# ftdi_ok.net
KiCad netlist of a schematic drawn in Altium Designer
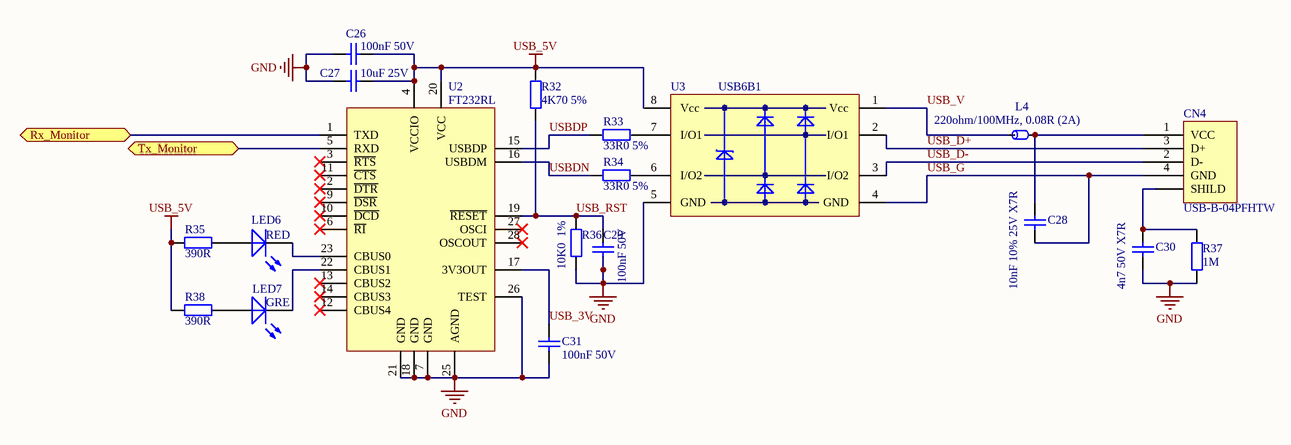
[diagram p0: ftdi_ok.SchDoc]

(export (version "E")
  (design (tool "Eeschema 10.0.6"))
  (components
    (comp (ref "C26")
      (value "100nF 50V")
      (footprint "0805_C")
      (description "SMD kondenzátorok")
      (libsource (lib "MERES") (part "Capacitor_SMD"))
    )
    (comp (ref "C27")
      (value "10uF 25V")
      (footprint "1206_C")
      (description "SMD kondenzátorok")
      (libsource (lib "MERES") (part "Capacitor_SMD"))
    )
    (comp (ref "C28")
      (value "10nF 10% 25V X7R")
      (footprint "1210_C")
      (description "SMD kondenzátorok")
      (libsource (lib "MERES") (part "Capacitor_SMD"))
    )
    (comp (ref "C29")
      (value "100nF 50V")
      (footprint "0805_C")
      (description "SMD kondenzátorok")
      (libsource (lib "MERES") (part "Capacitor_SMD"))
    )
    (comp (ref "C30")
      (value "4n7 50V X7R")
      (footprint "0805_C")
      (description "SMD kondenzátorok")
      (libsource (lib "MERES") (part "Capacitor_SMD"))
    )
    (comp (ref "C31")
      (value "100nF 50V")
      (footprint "0805_C")
      (description "SMD kondenzátorok")
      (libsource (lib "MERES") (part "Capacitor_SMD"))
    )
    (comp (ref "CN4") (value "USB-B-04PFHTW") (footprint "USB-B") (libsource (lib "MERES") (part "USB-B")))
    (comp (ref "L4")
      (value "220ohm/100MHz, 0.08R (2A)")
      (footprint "0805_R")
      (description "SMD Ferrit Bead 220ohm/100MHz")
      (libsource (lib "MERES") (part "Ferrit Bead"))
    )
    (comp (ref "LED6")
      (value "RED")
      (footprint "FP_LED_TH_RED")
      (description "LED")
      (libsource (lib "hallglib") (part "LED"))
    )
    (comp (ref "LED7")
      (value "GRE")
      (footprint "FP_LED_TH_GREEN")
      (description "LED")
      (libsource (lib "hallglib") (part "LED"))
    )
    (comp (ref "R32") (value "4K70 5%") (footprint "AXIAL-0.3") (libsource (lib "") (part "Resistor_2")))
    (comp (ref "R33")
      (value "33R0 5%")
      (footprint "AXIAL-0.3")
      (libsource (lib "hallglib") (part "Resistor"))
    )
    (comp (ref "R34")
      (value "33R0 5%")
      (footprint "AXIAL-0.3")
      (libsource (lib "hallglib") (part "Resistor"))
    )
    (comp (ref "R35") (value "390R") (footprint "AXIAL-0.3") (libsource (lib "") (part "Resistor_1")))
    (comp (ref "R36") (value "10K0  1%") (footprint "AXIAL-0.3") (libsource (lib "") (part "Resistor_2")))
    (comp (ref "R37") (value "1M") (footprint "0805_R") (libsource (lib "") (part "Resistor_3")))
    (comp (ref "R38") (value "390R") (footprint "AXIAL-0.3") (libsource (lib "") (part "Resistor_1")))
    (comp (ref "U2")
      (value "FT232RL")
      (footprint "SSOP-28")
      (description "USB - UART IC")
      (libsource (lib "MERES") (part "FT232RL"))
    )
    (comp (ref "U3") (value "USB6B1") (footprint "SO-8") (libsource (lib "MERES") (part "USB6B1")))
  )
  (nets
    (net (code "1") (name "/Rx_Monitor") (class "Default")
      (node (ref "U2") (pin "1") (pinfunction "TXD_1") (pintype "passive"))
    )
    (net (code "2") (name "/Tx_Monitor") (class "Default")
      (node (ref "U2") (pin "5") (pinfunction "RXD_5") (pintype "passive"))
    )
    (net (code "3") (name "/USBDN") (class "Default")
      (node (ref "R34") (pin "2") (pinfunction "2_2") (pintype "passive"))
      (node (ref "U2") (pin "16") (pinfunction "USBDM_16") (pintype "passive"))
    )
    (net (code "4") (name "/USBDP") (class "Default")
      (node (ref "R33") (pin "2") (pinfunction "2_2") (pintype "passive"))
      (node (ref "U2") (pin "15") (pinfunction "USBDP_15") (pintype "passive"))
    )
    (net (code "5") (name "/USB_3V") (class "Default")
      (node (ref "C31") (pin "1") (pinfunction "1_1") (pintype "passive"))
      (node (ref "U2") (pin "17") (pinfunction "3V3OUT_17") (pintype "passive"))
    )
    (net (code "6") (name "/USB_D+") (class "Default")
      (node (ref "CN4") (pin "3") (pinfunction "D+_3") (pintype "passive"))
      (node (ref "U3") (pin "2") (pinfunction "I/O1_2") (pintype "passive"))
    )
    (net (code "7") (name "/USB_D-") (class "Default")
      (node (ref "CN4") (pin "2") (pinfunction "D-_2") (pintype "passive"))
      (node (ref "U3") (pin "3") (pinfunction "I/O2_3") (pintype "passive"))
    )
    (net (code "8") (name "/USB_G") (class "Default")
      (node (ref "C28") (pin "2") (pinfunction "2_2") (pintype "passive"))
      (node (ref "CN4") (pin "4") (pinfunction "GND_4") (pintype "passive"))
      (node (ref "U3") (pin "4") (pinfunction "GND_4") (pintype "passive"))
    )
    (net (code "9") (name "/USB_RST") (class "Default")
      (node (ref "C29") (pin "1") (pinfunction "1_1") (pintype "passive"))
      (node (ref "R32") (pin "1") (pinfunction "1_1") (pintype "passive"))
      (node (ref "R36") (pin "2") (pinfunction "2_2") (pintype "passive"))
      (node (ref "U2") (pin "19") (pinfunction "~{RESET}_19") (pintype "passive"))
    )
    (net (code "10") (name "/USB_V") (class "Default")
      (node (ref "L4") (pin "2") (pinfunction "2_2") (pintype "passive"))
      (node (ref "U3") (pin "1") (pinfunction "Vcc_1") (pintype "passive"))
    )
    (net (code "11") (name "GND") (class "Default")
      (node (ref "C26") (pin "2") (pinfunction "2_2") (pintype "passive"))
      (node (ref "C27") (pin "2") (pinfunction "2_2") (pintype "passive"))
      (node (ref "C29") (pin "2") (pinfunction "2_2") (pintype "passive"))
      (node (ref "C30") (pin "2") (pinfunction "2_2") (pintype "passive"))
      (node (ref "C31") (pin "2") (pinfunction "2_2") (pintype "passive"))
      (node (ref "R36") (pin "1") (pinfunction "1_1") (pintype "passive"))
      (node (ref "R37") (pin "2") (pinfunction "2_2") (pintype "passive"))
      (node (ref "U2") (pin "18") (pinfunction "GND_18") (pintype "passive"))
      (node (ref "U2") (pin "21") (pinfunction "GND_21") (pintype "passive"))
      (node (ref "U2") (pin "25") (pinfunction "AGND_25") (pintype "passive"))
      (node (ref "U2") (pin "26") (pinfunction "TEST_26") (pintype "passive"))
      (node (ref "U2") (pin "7") (pinfunction "GND_7") (pintype "passive"))
      (node (ref "U3") (pin "5") (pinfunction "GND_5") (pintype "passive"))
    )
    (net (code "12") (name "Net-(CN4-SHILD)") (class "Default")
      (node (ref "C30") (pin "1") (pinfunction "1_1") (pintype "passive"))
      (node (ref "CN4") (pin "0") (pinfunction "SHILD_0") (pintype "passive"))
      (node (ref "R37") (pin "1") (pinfunction "1_1") (pintype "passive"))
    )
    (net (code "13") (name "Net-(CN4-VCC)") (class "Default")
      (node (ref "C28") (pin "1") (pinfunction "1_1") (pintype "passive"))
      (node (ref "CN4") (pin "1") (pinfunction "VCC_1") (pintype "passive"))
      (node (ref "L4") (pin "1") (pinfunction "1_1") (pintype "passive"))
    )
    (net (code "14") (name "Net-(LED6-A)") (class "Default")
      (node (ref "LED6") (pin "1") (pinfunction "A_1") (pintype "passive"))
      (node (ref "R35") (pin "2") (pinfunction "2_2") (pintype "passive"))
    )
    (net (code "15") (name "Net-(LED6-K)") (class "Default")
      (node (ref "LED6") (pin "2") (pinfunction "K_2") (pintype "passive"))
      (node (ref "U2") (pin "23") (pinfunction "CBUS0_23") (pintype "passive"))
    )
    (net (code "16") (name "Net-(LED7-A)") (class "Default")
      (node (ref "LED7") (pin "1") (pinfunction "A_1") (pintype "passive"))
      (node (ref "R38") (pin "2") (pinfunction "2_2") (pintype "passive"))
    )
    (net (code "17") (name "Net-(LED7-K)") (class "Default")
      (node (ref "LED7") (pin "2") (pinfunction "K_2") (pintype "passive"))
      (node (ref "U2") (pin "22") (pinfunction "CBUS1_22") (pintype "passive"))
    )
    (net (code "18") (name "Net-(R33-Pad1)") (class "Default")
      (node (ref "R33") (pin "1") (pinfunction "1_1") (pintype "passive"))
      (node (ref "U3") (pin "7") (pinfunction "I/O1_7") (pintype "passive"))
    )
    (net (code "19") (name "Net-(R34-Pad1)") (class "Default")
      (node (ref "R34") (pin "1") (pinfunction "1_1") (pintype "passive"))
      (node (ref "U3") (pin "6") (pinfunction "I/O2_6") (pintype "passive"))
    )
    (net (code "20") (name "USB_5V") (class "Default")
      (node (ref "C26") (pin "1") (pinfunction "1_1") (pintype "passive"))
      (node (ref "C27") (pin "1") (pinfunction "1_1") (pintype "passive"))
      (node (ref "R32") (pin "2") (pinfunction "2_2") (pintype "passive"))
      (node (ref "R35") (pin "1") (pinfunction "1_1") (pintype "passive"))
      (node (ref "R38") (pin "1") (pinfunction "1_1") (pintype "passive"))
      (node (ref "U2") (pin "20") (pinfunction "VCC_20") (pintype "passive"))
      (node (ref "U2") (pin "4") (pinfunction "VCCIO_4") (pintype "passive"))
      (node (ref "U3") (pin "8") (pinfunction "Vcc_8") (pintype "passive"))
    )
    (net (code "21") (name "unconnected-(U2-CBUS2-Pad13)") (class "Default")
      (node (ref "U2") (pin "13") (pinfunction "CBUS2_13") (pintype "passive+no_connect"))
    )
    (net (code "22") (name "unconnected-(U2-CBUS3-Pad14)") (class "Default")
      (node (ref "U2") (pin "14") (pinfunction "CBUS3_14") (pintype "passive+no_connect"))
    )
    (net (code "23") (name "unconnected-(U2-CBUS4-Pad12)") (class "Default")
      (node (ref "U2") (pin "12") (pinfunction "CBUS4_12") (pintype "passive+no_connect"))
    )
    (net (code "24") (name "unconnected-(U2-OSCI-Pad27)") (class "Default")
      (node (ref "U2") (pin "27") (pinfunction "OSCI_27") (pintype "passive+no_connect"))
    )
    (net (code "25") (name "unconnected-(U2-OSCOUT-Pad28)") (class "Default")
      (node (ref "U2") (pin "28") (pinfunction "OSCOUT_28") (pintype "passive+no_connect"))
    )
    (net (code "26") (name "unconnected-(U2-~{CTS}-Pad11)") (class "Default")
      (node (ref "U2") (pin "11") (pinfunction "~{CTS}_11") (pintype "passive+no_connect"))
    )
    (net (code "27") (name "unconnected-(U2-~{DCD}-Pad10)") (class "Default")
      (node (ref "U2") (pin "10") (pinfunction "~{DCD}_10") (pintype "passive+no_connect"))
    )
    (net (code "28") (name "unconnected-(U2-~{DSR}-Pad9)") (class "Default")
      (node (ref "U2") (pin "9") (pinfunction "~{DSR}_9") (pintype "passive+no_connect"))
    )
    (net (code "29") (name "unconnected-(U2-~{DTR}-Pad2)") (class "Default")
      (node (ref "U2") (pin "2") (pinfunction "~{DTR}_2") (pintype "passive+no_connect"))
    )
    (net (code "30") (name "unconnected-(U2-~{RI}-Pad6)") (class "Default")
      (node (ref "U2") (pin "6") (pinfunction "~{RI}_6") (pintype "passive+no_connect"))
    )
    (net (code "31") (name "unconnected-(U2-~{RTS}-Pad3)") (class "Default")
      (node (ref "U2") (pin "3") (pinfunction "~{RTS}_3") (pintype "passive+no_connect"))
    )
  )
)
